# Board_MCU.net
KiCad netlist of a schematic drawn in Altium Designer
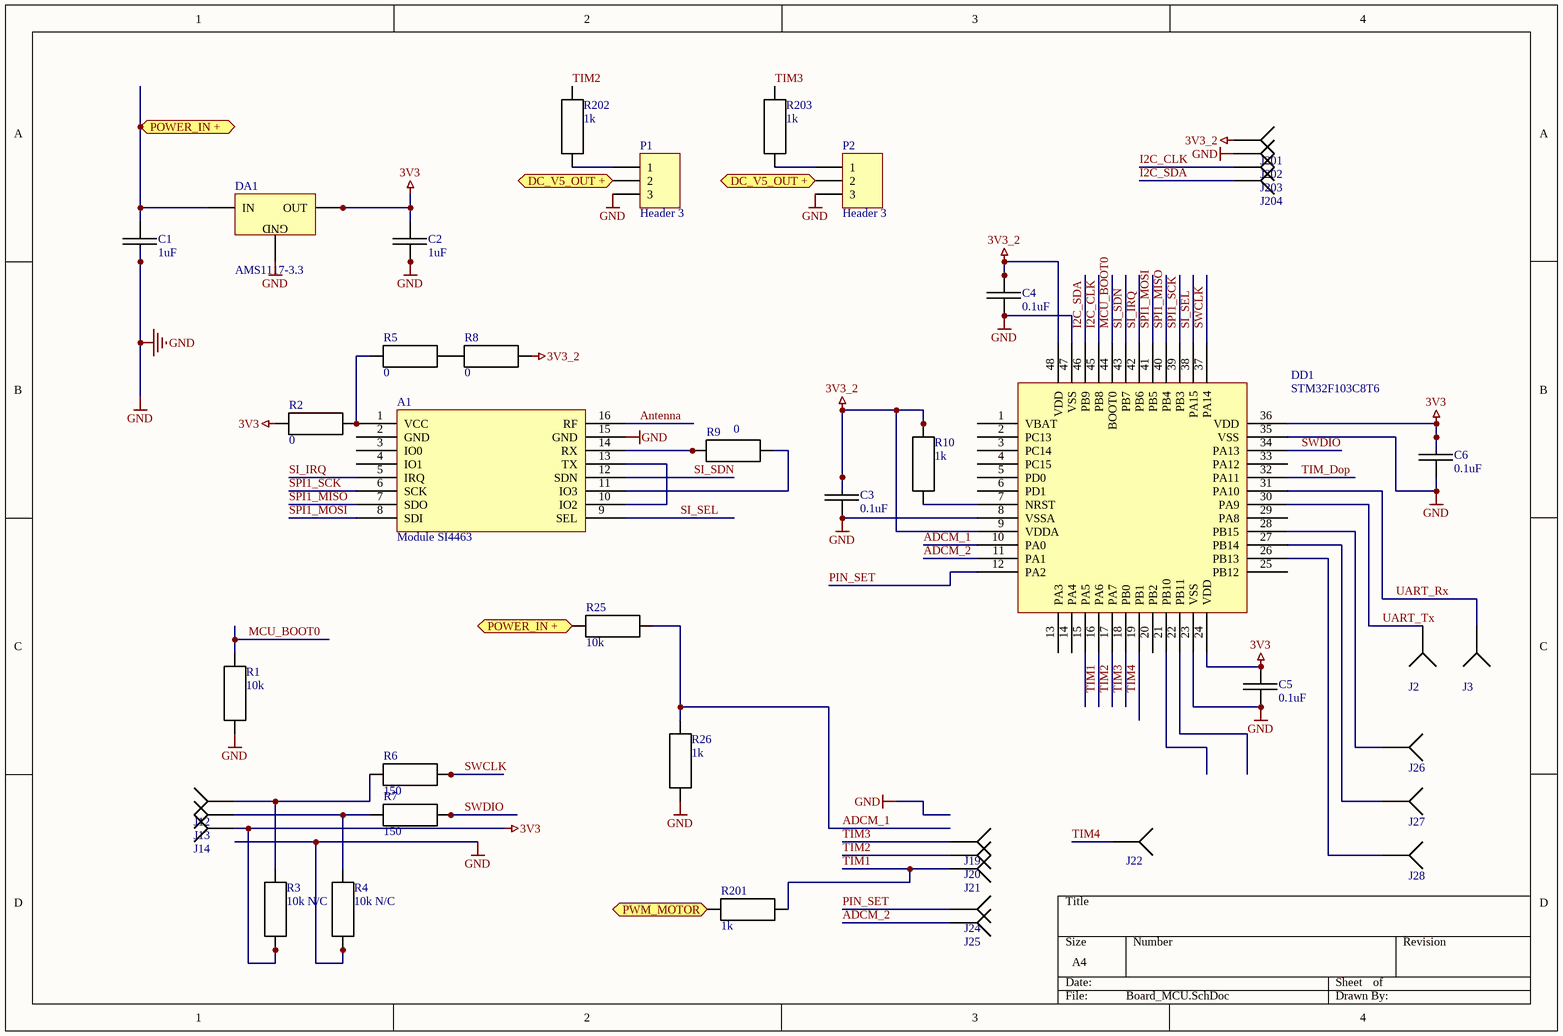
[diagram p0: Board_MCU.SchDoc]

(export (version "E")
  (design (tool "Eeschema 10.0.6"))
  (components
    (comp (ref "A1")
      (value "Module SI4463")
      (footprint "MODULE_SI44663")
      (libsource (lib "Schlib1") (part "module_SI4463"))
    )
    (comp (ref "C1")
      (value "1uF")
      (footprint "CAP0805")
      (fields (field (name "VOLTAGE") "50V"))
      (libsource (lib "Schlib1") (part "Capacitor"))
    )
    (comp (ref "C2")
      (value "1uF")
      (footprint "CAP0805")
      (fields (field (name "VOLTAGE") "50V"))
      (libsource (lib "Schlib1") (part "Capacitor"))
    )
    (comp (ref "C3")
      (value "0.1uF")
      (footprint "CAP0805")
      (fields (field (name "VOLTAGE") "50V"))
      (libsource (lib "Schlib1") (part "Capacitor"))
    )
    (comp (ref "C4")
      (value "0.1uF")
      (footprint "CAP0805")
      (fields (field (name "VOLTAGE") "50V"))
      (libsource (lib "Schlib1") (part "Capacitor"))
    )
    (comp (ref "C5")
      (value "0.1uF")
      (footprint "CAP0805")
      (fields (field (name "VOLTAGE") "50V"))
      (libsource (lib "Schlib1") (part "Capacitor"))
    )
    (comp (ref "C6")
      (value "0.1uF")
      (footprint "CAP0805")
      (fields (field (name "VOLTAGE") "50V"))
      (libsource (lib "Schlib1") (part "Capacitor"))
    )
    (comp (ref "DA1")
      (value "AMS1117-3.3")
      (footprint "SOT-223")
      (description "LDO 3.3V 0.5A")
      (libsource (lib "Schlib1") (part "DA-AMS1117"))
    )
    (comp (ref "DD1")
      (value "STM32F103C8T6")
      (footprint "STM32L151C")
      (description "LQFP48")
      (libsource (lib "Schlib1") (part "STM32F103C8T6"))
    )
    (comp (ref "J2") (value "X-Socket") (footprint "Socket") (libsource (lib "Schlib1") (part "X-Socket")))
    (comp (ref "J3") (value "X-Socket") (footprint "Socket") (libsource (lib "Schlib1") (part "X-Socket")))
    (comp (ref "J12") (value "X-Socket") (footprint "Socket") (libsource (lib "Schlib1") (part "X-Socket")))
    (comp (ref "J13") (value "X-Socket") (footprint "Socket") (libsource (lib "Schlib1") (part "X-Socket")))
    (comp (ref "J14") (value "X-Socket") (footprint "Socket") (libsource (lib "Schlib1") (part "X-Socket")))
    (comp (ref "J19") (value "X-Socket") (footprint "Socket") (libsource (lib "Schlib1") (part "X-Socket")))
    (comp (ref "J20") (value "X-Socket") (footprint "Socket") (libsource (lib "Schlib1") (part "X-Socket")))
    (comp (ref "J21") (value "X-Socket") (footprint "Socket") (libsource (lib "Schlib1") (part "X-Socket")))
    (comp (ref "J22") (value "X-Socket") (footprint "Socket") (libsource (lib "Schlib1") (part "X-Socket")))
    (comp (ref "J24") (value "X-Socket") (footprint "Socket") (libsource (lib "Schlib1") (part "X-Socket")))
    (comp (ref "J25") (value "X-Socket") (footprint "Socket") (libsource (lib "Schlib1") (part "X-Socket")))
    (comp (ref "J26") (value "X-Socket") (footprint "Socket") (libsource (lib "Schlib1") (part "X-Socket")))
    (comp (ref "J27") (value "X-Socket") (footprint "Socket") (libsource (lib "Schlib1") (part "X-Socket")))
    (comp (ref "J28") (value "X-Socket") (footprint "Socket") (libsource (lib "Schlib1") (part "X-Socket")))
    (comp (ref "J201") (value "X-Socket") (footprint "Socket") (libsource (lib "Schlib1") (part "X-Socket")))
    (comp (ref "J202") (value "X-Socket") (footprint "Socket") (libsource (lib "Schlib1") (part "X-Socket")))
    (comp (ref "J203") (value "X-Socket") (footprint "Socket") (libsource (lib "Schlib1") (part "X-Socket")))
    (comp (ref "J204") (value "X-Socket") (footprint "Socket") (libsource (lib "Schlib1") (part "X-Socket")))
    (comp (ref "P1")
      (value "Header 3")
      (footprint "HDR1X3")
      (description "Header, 3-Pin")
      (fields (field (name "PUBLISHER") "Altium Limited"))
      (libsource (lib "Miscellaneous Connectors") (part "Header 3"))
    )
    (comp (ref "P2")
      (value "Header 3")
      (footprint "HDR1X3")
      (description "Header, 3-Pin")
      (fields (field (name "PUBLISHER") "Altium Limited"))
      (libsource (lib "Miscellaneous Connectors") (part "Header 3"))
    )
    (comp (ref "R1") (value "10k") (footprint "RES0805") (libsource (lib "") (part "Resistor_1")))
    (comp (ref "R2") (value "0") (footprint "RES0805") (libsource (lib "Schlib1") (part "Resistor")))
    (comp (ref "R3") (value "10k N/C") (footprint "RES0603") (libsource (lib "") (part "Resistor_1")))
    (comp (ref "R4") (value "10k N/C") (footprint "RES0603") (libsource (lib "") (part "Resistor_1")))
    (comp (ref "R5") (value "0") (footprint "RES0805") (libsource (lib "Schlib1") (part "Resistor")))
    (comp (ref "R6") (value "150") (footprint "RES0603") (libsource (lib "") (part "Resistor_3")))
    (comp (ref "R7") (value "150") (footprint "RES0603") (libsource (lib "") (part "Resistor_3")))
    (comp (ref "R8") (value "0") (footprint "RES0805") (libsource (lib "Schlib1") (part "Resistor")))
    (comp (ref "R9") (value "0") (footprint "RES0603") (libsource (lib "Schlib1") (part "Resistor")))
    (comp (ref "R10") (value "1k") (footprint "RES0805") (libsource (lib "") (part "Resistor_1")))
    (comp (ref "R25") (value "10k") (footprint "RES0805") (libsource (lib "Schlib1") (part "Resistor")))
    (comp (ref "R26") (value "1k") (footprint "RES0805") (libsource (lib "") (part "Resistor_1")))
    (comp (ref "R201") (value "1k") (footprint "RES0805") (libsource (lib "Schlib1") (part "Resistor")))
    (comp (ref "R202") (value "1k") (footprint "RES0805") (libsource (lib "") (part "Resistor_2")))
    (comp (ref "R203") (value "1k") (footprint "RES0805") (libsource (lib "") (part "Resistor_2")))
  )
  (nets
    (net (code "1") (name "/ADCM_1") (class "Default")
      (node (ref "DD1") (pin "10") (pinfunction "PA0_10") (pintype "passive"))
      (node (ref "R25") (pin "2") (pinfunction "2_2") (pintype "passive"))
      (node (ref "R26") (pin "1") (pinfunction "1_1") (pintype "passive"))
    )
    (net (code "2") (name "/ADCM_2") (class "Default")
      (node (ref "DD1") (pin "11") (pinfunction "PA1_11") (pintype "passive"))
      (node (ref "J25") (pin "1") (pinfunction "1_1") (pintype "passive"))
    )
    (net (code "3") (name "/Antenna") (class "Default")
      (node (ref "A1") (pin "16") (pinfunction "RF_16") (pintype "passive"))
    )
    (net (code "4") (name "/DC_V5_OUT +") (class "Default")
      (node (ref "P1") (pin "2") (pinfunction "2_2") (pintype "passive"))
      (node (ref "P2") (pin "2") (pinfunction "2_2") (pintype "passive"))
    )
    (net (code "5") (name "/I2C_CLK") (class "Default")
      (node (ref "DD1") (pin "45") (pinfunction "PB8_45") (pintype "passive"))
      (node (ref "J203") (pin "1") (pinfunction "1_1") (pintype "passive"))
    )
    (net (code "6") (name "/I2C_SDA") (class "Default")
      (node (ref "DD1") (pin "46") (pinfunction "PB9_46") (pintype "passive"))
      (node (ref "J204") (pin "1") (pinfunction "1_1") (pintype "passive"))
    )
    (net (code "7") (name "/MCU_BOOT0") (class "Default")
      (node (ref "DD1") (pin "44") (pinfunction "BOOT0_44") (pintype "passive"))
      (node (ref "R1") (pin "1") (pinfunction "1_1") (pintype "passive"))
    )
    (net (code "8") (name "/PIN_SET") (class "Default")
      (node (ref "DD1") (pin "12") (pinfunction "PA2_12") (pintype "passive"))
      (node (ref "J24") (pin "1") (pinfunction "1_1") (pintype "passive"))
    )
    (net (code "9") (name "/POWER_IN +") (class "Default")
      (node (ref "C1") (pin "1") (pinfunction "1_1") (pintype "passive"))
      (node (ref "DA1") (pin "3") (pinfunction "IN_3") (pintype "passive"))
      (node (ref "R25") (pin "1") (pinfunction "1_1") (pintype "passive"))
    )
    (net (code "10") (name "/PWM_MOTOR") (class "Default")
      (node (ref "R201") (pin "1") (pinfunction "1_1") (pintype "passive"))
    )
    (net (code "11") (name "/SI_IRQ") (class "Default")
      (node (ref "A1") (pin "5") (pinfunction "IRQ_5") (pintype "passive"))
      (node (ref "DD1") (pin "42") (pinfunction "PB6_42") (pintype "passive"))
    )
    (net (code "12") (name "/SI_SDN") (class "Default")
      (node (ref "A1") (pin "12") (pinfunction "SDN_12") (pintype "passive"))
      (node (ref "DD1") (pin "43") (pinfunction "PB7_43") (pintype "passive"))
    )
    (net (code "13") (name "/SI_SEL") (class "Default")
      (node (ref "A1") (pin "9") (pinfunction "SEL_9") (pintype "passive"))
      (node (ref "DD1") (pin "38") (pinfunction "PA15_38") (pintype "passive"))
    )
    (net (code "14") (name "/SPI1_MISO") (class "Default")
      (node (ref "A1") (pin "7") (pinfunction "SDO_7") (pintype "passive"))
      (node (ref "DD1") (pin "40") (pinfunction "PB4_40") (pintype "passive"))
    )
    (net (code "15") (name "/SPI1_MOSI") (class "Default")
      (node (ref "A1") (pin "8") (pinfunction "SDI_8") (pintype "passive"))
      (node (ref "DD1") (pin "41") (pinfunction "PB5_41") (pintype "passive"))
    )
    (net (code "16") (name "/SPI1_SCK") (class "Default")
      (node (ref "A1") (pin "6") (pinfunction "SCK_6") (pintype "passive"))
      (node (ref "DD1") (pin "39") (pinfunction "PB3_39") (pintype "passive"))
    )
    (net (code "17") (name "/SWCLK") (class "Default")
      (node (ref "DD1") (pin "37") (pinfunction "PA14_37") (pintype "passive"))
      (node (ref "R6") (pin "1") (pinfunction "1_1") (pintype "passive"))
    )
    (net (code "18") (name "/SWDIO") (class "Default")
      (node (ref "DD1") (pin "34") (pinfunction "PA13_34") (pintype "passive"))
      (node (ref "R7") (pin "1") (pinfunction "1_1") (pintype "passive"))
    )
    (net (code "19") (name "/TIM1") (class "Default")
      (node (ref "DD1") (pin "16") (pinfunction "PA6_16") (pintype "passive"))
      (node (ref "J21") (pin "1") (pinfunction "1_1") (pintype "passive"))
      (node (ref "R201") (pin "2") (pinfunction "2_2") (pintype "passive"))
    )
    (net (code "20") (name "/TIM2") (class "Default")
      (node (ref "DD1") (pin "17") (pinfunction "PA7_17") (pintype "passive"))
      (node (ref "J20") (pin "1") (pinfunction "1_1") (pintype "passive"))
      (node (ref "R202") (pin "2") (pinfunction "2_2") (pintype "passive"))
    )
    (net (code "21") (name "/TIM3") (class "Default")
      (node (ref "DD1") (pin "18") (pinfunction "PB0_18") (pintype "passive"))
      (node (ref "J19") (pin "1") (pinfunction "1_1") (pintype "passive"))
      (node (ref "R203") (pin "2") (pinfunction "2_2") (pintype "passive"))
    )
    (net (code "22") (name "/TIM4") (class "Default")
      (node (ref "DD1") (pin "19") (pinfunction "PB1_19") (pintype "passive"))
      (node (ref "J22") (pin "1") (pinfunction "1_1") (pintype "passive"))
    )
    (net (code "23") (name "/TIM_Dop") (class "Default")
      (node (ref "DD1") (pin "32") (pinfunction "PA11_32") (pintype "passive"))
    )
    (net (code "24") (name "/UART_Rx") (class "Default")
      (node (ref "DD1") (pin "31") (pinfunction "PA10_31") (pintype "passive"))
      (node (ref "J3") (pin "1") (pinfunction "1_1") (pintype "passive"))
    )
    (net (code "25") (name "/UART_Tx") (class "Default")
      (node (ref "DD1") (pin "30") (pinfunction "PA9_30") (pintype "passive"))
      (node (ref "J2") (pin "1") (pinfunction "1_1") (pintype "passive"))
    )
    (net (code "26") (name "3V3") (class "Default")
      (node (ref "C2") (pin "1") (pinfunction "1_1") (pintype "passive"))
      (node (ref "C5") (pin "1") (pinfunction "1_1") (pintype "passive"))
      (node (ref "C6") (pin "1") (pinfunction "1_1") (pintype "passive"))
      (node (ref "DA1") (pin "2") (pinfunction "OUT_2") (pintype "passive"))
      (node (ref "DA1") (pin "4") (pinfunction "4_4") (pintype "passive"))
      (node (ref "DD1") (pin "24") (pinfunction "VDD_24") (pintype "passive"))
      (node (ref "DD1") (pin "36") (pinfunction "VDD_36") (pintype "passive"))
      (node (ref "J14") (pin "1") (pinfunction "1_1") (pintype "passive"))
      (node (ref "R2") (pin "1") (pinfunction "1_1") (pintype "passive"))
      (node (ref "R3") (pin "2") (pinfunction "2_2") (pintype "passive"))
    )
    (net (code "27") (name "3V3_2") (class "Default")
      (node (ref "C3") (pin "1") (pinfunction "1_1") (pintype "passive"))
      (node (ref "C4") (pin "1") (pinfunction "1_1") (pintype "passive"))
      (node (ref "DD1") (pin "48") (pinfunction "VDD_48") (pintype "passive"))
      (node (ref "DD1") (pin "9") (pinfunction "VDDA_9") (pintype "passive"))
      (node (ref "J201") (pin "1") (pinfunction "1_1") (pintype "passive"))
      (node (ref "R10") (pin "1") (pinfunction "1_1") (pintype "passive"))
      (node (ref "R8") (pin "2") (pinfunction "2_2") (pintype "passive"))
    )
    (net (code "28") (name "GND") (class "Default")
      (node (ref "A1") (pin "15") (pinfunction "GND_15") (pintype "passive"))
      (node (ref "C1") (pin "2") (pinfunction "2_2") (pintype "passive"))
      (node (ref "C2") (pin "2") (pinfunction "2_2") (pintype "passive"))
      (node (ref "C3") (pin "2") (pinfunction "2_2") (pintype "passive"))
      (node (ref "C4") (pin "2") (pinfunction "2_2") (pintype "passive"))
      (node (ref "C5") (pin "2") (pinfunction "2_2") (pintype "passive"))
      (node (ref "C6") (pin "2") (pinfunction "2_2") (pintype "passive"))
      (node (ref "DA1") (pin "1") (pinfunction "GND_1") (pintype "passive"))
      (node (ref "DD1") (pin "23") (pinfunction "VSS_23") (pintype "passive"))
      (node (ref "DD1") (pin "35") (pinfunction "VSS_35") (pintype "passive"))
      (node (ref "DD1") (pin "47") (pinfunction "VSS_47") (pintype "passive"))
      (node (ref "DD1") (pin "8") (pinfunction "VSSA_8") (pintype "passive"))
      (node (ref "J202") (pin "1") (pinfunction "1_1") (pintype "passive"))
      (node (ref "P1") (pin "3") (pinfunction "3_3") (pintype "passive"))
      (node (ref "P2") (pin "3") (pinfunction "3_3") (pintype "passive"))
      (node (ref "R1") (pin "2") (pinfunction "2_2") (pintype "passive"))
      (node (ref "R26") (pin "2") (pinfunction "2_2") (pintype "passive"))
      (node (ref "R4") (pin "2") (pinfunction "2_2") (pintype "passive"))
    )
    (net (code "29") (name "Net-(A1-IO2)") (class "Default")
      (node (ref "A1") (pin "10") (pinfunction "IO2_10") (pintype "passive"))
      (node (ref "A1") (pin "13") (pinfunction "TX_13") (pintype "passive"))
    )
    (net (code "30") (name "Net-(A1-IO3)") (class "Default")
      (node (ref "A1") (pin "11") (pinfunction "IO3_11") (pintype "passive"))
      (node (ref "R9") (pin "2") (pinfunction "2_2") (pintype "passive"))
    )
    (net (code "31") (name "Net-(A1-RX)") (class "Default")
      (node (ref "A1") (pin "14") (pinfunction "RX_14") (pintype "passive"))
      (node (ref "R9") (pin "1") (pinfunction "1_1") (pintype "passive"))
    )
    (net (code "32") (name "Net-(A1-VCC)") (class "Default")
      (node (ref "A1") (pin "1") (pinfunction "VCC_1") (pintype "passive"))
      (node (ref "R2") (pin "2") (pinfunction "2_2") (pintype "passive"))
      (node (ref "R5") (pin "1") (pinfunction "1_1") (pintype "passive"))
    )
    (net (code "33") (name "Net-(DD1-NRST)") (class "Default")
      (node (ref "DD1") (pin "7") (pinfunction "NRST_7") (pintype "passive"))
      (node (ref "R10") (pin "2") (pinfunction "2_2") (pintype "passive"))
    )
    (net (code "34") (name "Net-(DD1-PB13)") (class "Default")
      (node (ref "DD1") (pin "26") (pinfunction "PB13_26") (pintype "passive"))
      (node (ref "J28") (pin "1") (pinfunction "1_1") (pintype "passive"))
    )
    (net (code "35") (name "Net-(DD1-PB14)") (class "Default")
      (node (ref "DD1") (pin "27") (pinfunction "PB14_27") (pintype "passive"))
      (node (ref "J27") (pin "1") (pinfunction "1_1") (pintype "passive"))
    )
    (net (code "36") (name "Net-(DD1-PB15)") (class "Default")
      (node (ref "DD1") (pin "28") (pinfunction "PB15_28") (pintype "passive"))
      (node (ref "J26") (pin "1") (pinfunction "1_1") (pintype "passive"))
    )
    (net (code "37") (name "Net-(J12-Pad1)") (class "Default")
      (node (ref "J12") (pin "1") (pinfunction "1_1") (pintype "passive"))
      (node (ref "R3") (pin "1") (pinfunction "1_1") (pintype "passive"))
      (node (ref "R6") (pin "2") (pinfunction "2_2") (pintype "passive"))
    )
    (net (code "38") (name "Net-(J13-Pad1)") (class "Default")
      (node (ref "J13") (pin "1") (pinfunction "1_1") (pintype "passive"))
      (node (ref "R4") (pin "1") (pinfunction "1_1") (pintype "passive"))
      (node (ref "R7") (pin "2") (pinfunction "2_2") (pintype "passive"))
    )
    (net (code "39") (name "Net-(P1-Pad1)") (class "Default")
      (node (ref "P1") (pin "1") (pinfunction "1_1") (pintype "passive"))
      (node (ref "R202") (pin "1") (pinfunction "1_1") (pintype "passive"))
    )
    (net (code "40") (name "Net-(P2-Pad1)") (class "Default")
      (node (ref "P2") (pin "1") (pinfunction "1_1") (pintype "passive"))
      (node (ref "R203") (pin "1") (pinfunction "1_1") (pintype "passive"))
    )
    (net (code "41") (name "Net-(R5-Pad2)") (class "Default")
      (node (ref "R5") (pin "2") (pinfunction "2_2") (pintype "passive"))
      (node (ref "R8") (pin "1") (pinfunction "1_1") (pintype "passive"))
    )
    (net (code "42") (name "unconnected-(A1-GND-Pad2)") (class "Default")
      (node (ref "A1") (pin "2") (pinfunction "GND_2") (pintype "passive"))
    )
    (net (code "43") (name "unconnected-(A1-IO0-Pad3)") (class "Default")
      (node (ref "A1") (pin "3") (pinfunction "IO0_3") (pintype "passive"))
    )
    (net (code "44") (name "unconnected-(A1-IO1-Pad4)") (class "Default")
      (node (ref "A1") (pin "4") (pinfunction "IO1_4") (pintype "passive"))
    )
    (net (code "45") (name "unconnected-(DD1-PA3-Pad13)") (class "Default")
      (node (ref "DD1") (pin "13") (pinfunction "PA3_13") (pintype "passive"))
    )
    (net (code "46") (name "unconnected-(DD1-PA4-Pad14)") (class "Default")
      (node (ref "DD1") (pin "14") (pinfunction "PA4_14") (pintype "passive"))
    )
    (net (code "47") (name "unconnected-(DD1-PA5-Pad15)") (class "Default")
      (node (ref "DD1") (pin "15") (pinfunction "PA5_15") (pintype "passive"))
    )
    (net (code "48") (name "unconnected-(DD1-PA8-Pad29)") (class "Default")
      (node (ref "DD1") (pin "29") (pinfunction "PA8_29") (pintype "passive"))
    )
    (net (code "49") (name "unconnected-(DD1-PA12-Pad33)") (class "Default")
      (node (ref "DD1") (pin "33") (pinfunction "PA12_33") (pintype "passive"))
    )
    (net (code "50") (name "unconnected-(DD1-PB2-Pad20)") (class "Default")
      (node (ref "DD1") (pin "20") (pinfunction "PB2_20") (pintype "passive"))
    )
    (net (code "51") (name "unconnected-(DD1-PB10-Pad21)") (class "Default")
      (node (ref "DD1") (pin "21") (pinfunction "PB10_21") (pintype "passive"))
    )
    (net (code "52") (name "unconnected-(DD1-PB11-Pad22)") (class "Default")
      (node (ref "DD1") (pin "22") (pinfunction "PB11_22") (pintype "passive"))
    )
    (net (code "53") (name "unconnected-(DD1-PB12-Pad25)") (class "Default")
      (node (ref "DD1") (pin "25") (pinfunction "PB12_25") (pintype "passive"))
    )
    (net (code "54") (name "unconnected-(DD1-PC13-Pad2)") (class "Default")
      (node (ref "DD1") (pin "2") (pinfunction "PC13_2") (pintype "passive"))
    )
    (net (code "55") (name "unconnected-(DD1-PC14-Pad3)") (class "Default")
      (node (ref "DD1") (pin "3") (pinfunction "PC14_3") (pintype "passive"))
    )
    (net (code "56") (name "unconnected-(DD1-PC15-Pad4)") (class "Default")
      (node (ref "DD1") (pin "4") (pinfunction "PC15_4") (pintype "passive"))
    )
    (net (code "57") (name "unconnected-(DD1-PD0-Pad5)") (class "Default")
      (node (ref "DD1") (pin "5") (pinfunction "PD0_5") (pintype "passive"))
    )
    (net (code "58") (name "unconnected-(DD1-PD1-Pad6)") (class "Default")
      (node (ref "DD1") (pin "6") (pinfunction "PD1_6") (pintype "passive"))
    )
    (net (code "59") (name "unconnected-(DD1-VBAT-Pad1)") (class "Default")
      (node (ref "DD1") (pin "1") (pinfunction "VBAT_1") (pintype "passive"))
    )
  )
)
